# final_schematic_power_consumption_board.net
KiCad netlist of a schematic drawn in EAGLE
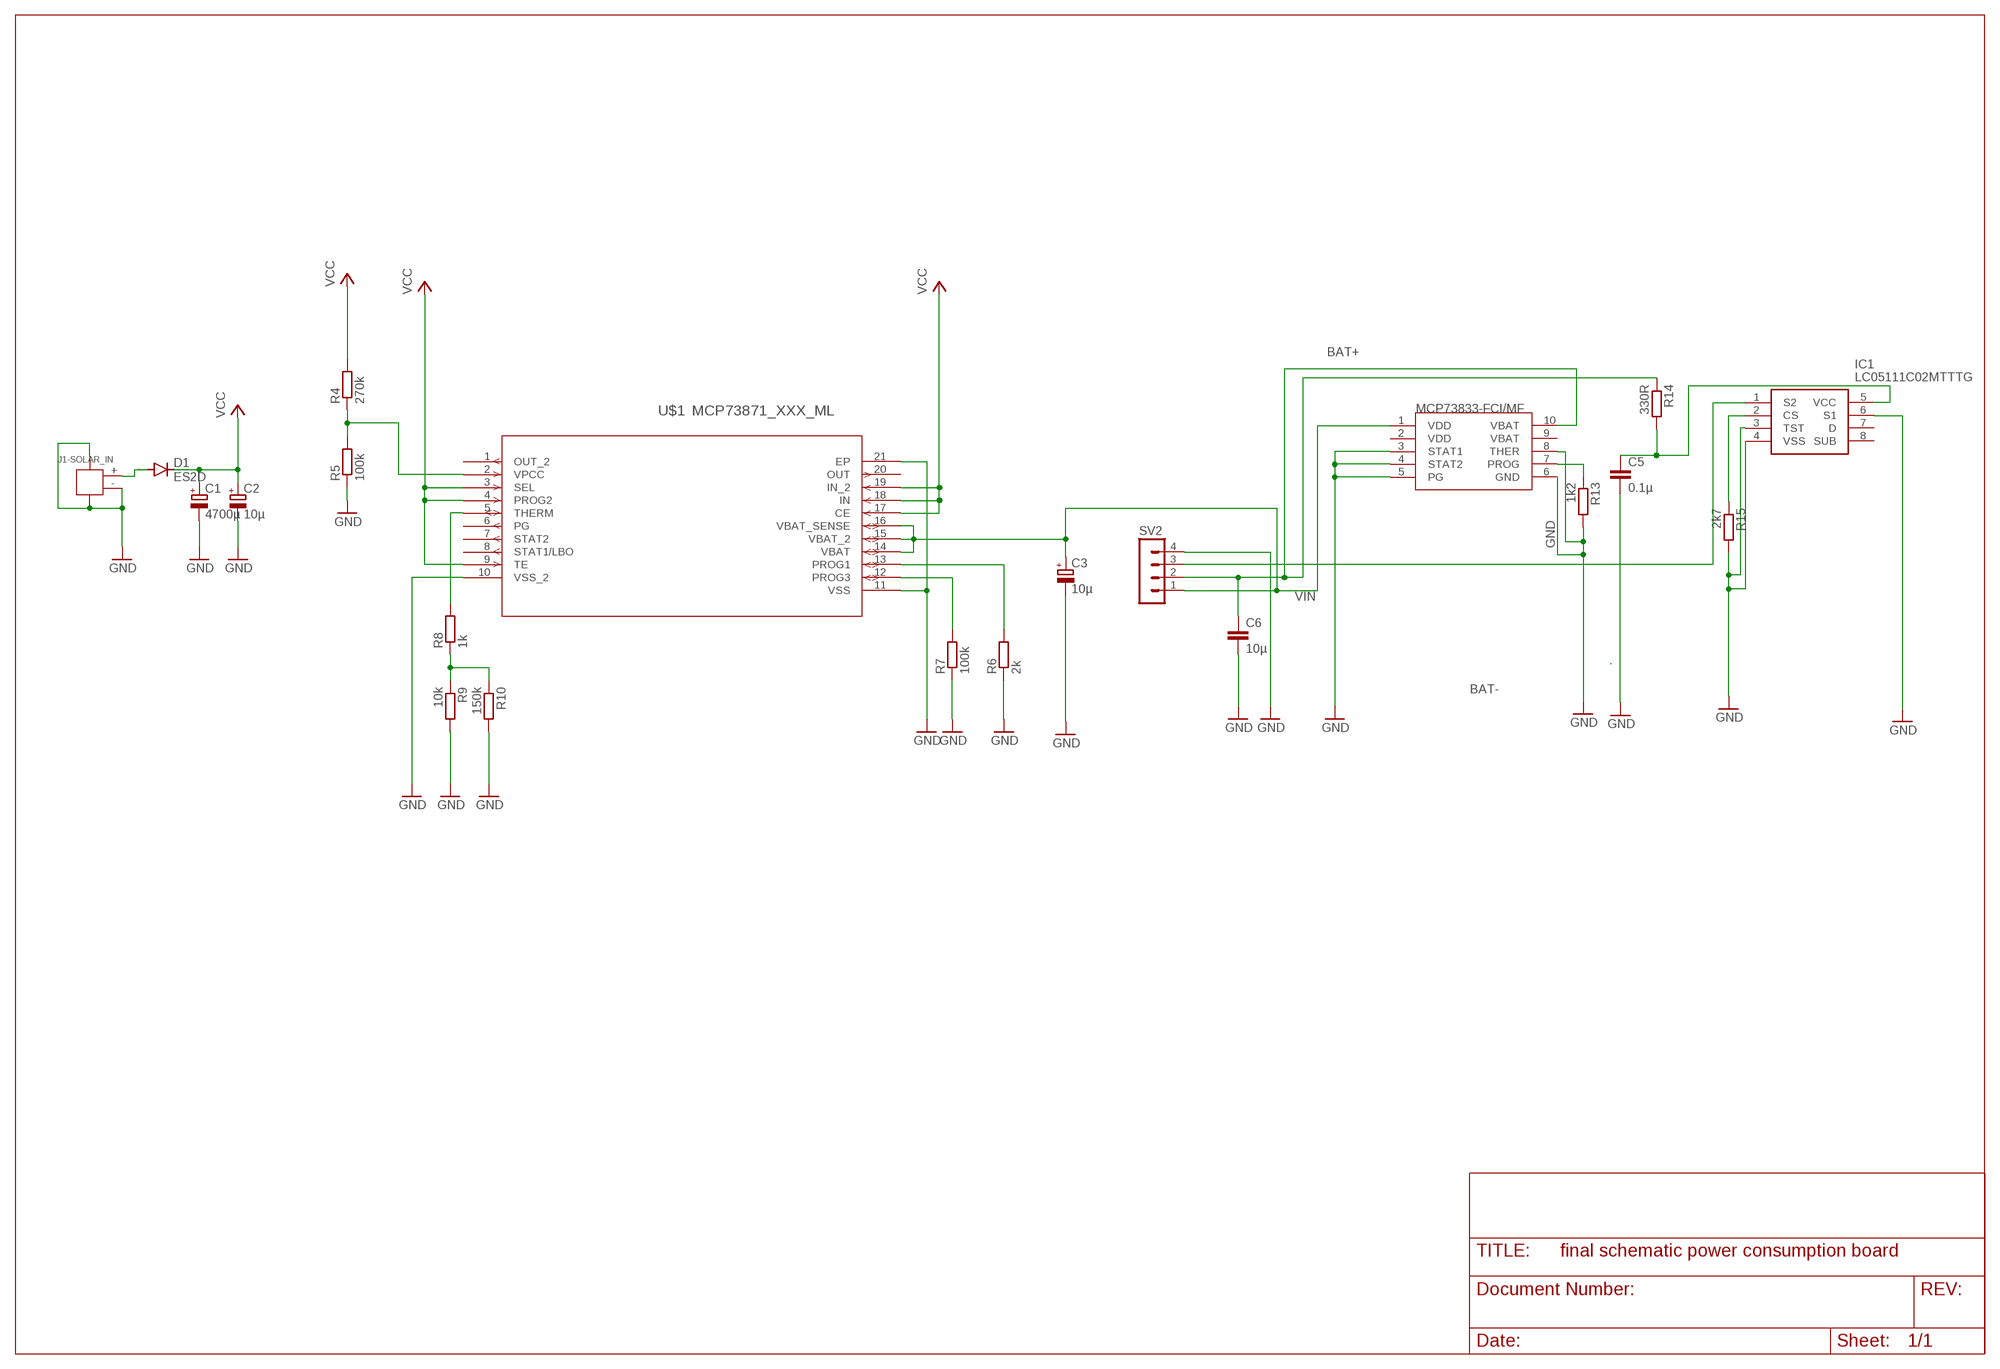
[diagram p0: schematic, sheet 1]

(export (version "E")
  (design (tool "Eeschema 10.0.6"))
  (components
    (comp (ref "C1")
      (value "4700µ")
      (footprint "eagle-import:153CLV-0505")
      (libsource (lib "eagle-import") (part "CPOL-EU153CLV-0505"))
    )
    (comp (ref "C2")
      (value "10µ")
      (footprint "eagle-import:153CLV-0505")
      (libsource (lib "eagle-import") (part "CPOL-EU153CLV-0505"))
    )
    (comp (ref "C3")
      (value "10µ")
      (footprint "eagle-import:153CLV-0505")
      (libsource (lib "eagle-import") (part "CPOL-EU153CLV-0505"))
    )
    (comp (ref "C5")
      (value "0.1µ")
      (footprint "eagle-import:C1206")
      (libsource (lib "eagle-import") (part "C-EUC1206"))
    )
    (comp (ref "C6")
      (value "10µ")
      (footprint "eagle-import:C1206")
      (libsource (lib "eagle-import") (part "C-EUC1206"))
    )
    (comp (ref "D1")
      (value "ES2D")
      (footprint "eagle-import:SMB")
      (libsource (lib "eagle-import") (part "ES2D"))
    )
    (comp (ref "IC1")
      (value "LC05111C02MTTTG")
      (footprint "eagle-import:LC05111C02MTTTG")
      (fields
        (field (name "MOUSER_PART_NUMBER") "863-LC05111C02MTTTG")
        (field (name "RS_PART_NUMBER") "8427787P")
      )
      (libsource (lib "eagle-import") (part "LC05111C02MTTTG"))
    )
    (comp (ref "J1-SOLAR_IN")
      (value "CONN-HEADER-SMD-PH-SIDE-(2P-2.0MM)")
      (footprint "eagle-import:HW2-SMD-2.0-90D")
      (libsource (lib "eagle-import") (part "CONN-HEADER-SMD-PH-SIDE-(2P-2.0MM)"))
    )
    (comp (ref "R4")
      (value "270k")
      (footprint "eagle-import:R0603")
      (libsource (lib "eagle-import") (part "R-EU_R0603"))
    )
    (comp (ref "R5")
      (value "100k")
      (footprint "eagle-import:R0603")
      (libsource (lib "eagle-import") (part "R-EU_R0603"))
    )
    (comp (ref "R6")
      (value "2k")
      (footprint "eagle-import:R0603")
      (libsource (lib "eagle-import") (part "R-EU_R0603"))
    )
    (comp (ref "R7")
      (value "100k")
      (footprint "eagle-import:R0603")
      (libsource (lib "eagle-import") (part "R-EU_R0603"))
    )
    (comp (ref "R8")
      (value "1k")
      (footprint "eagle-import:R0603")
      (libsource (lib "eagle-import") (part "R-EU_R0603"))
    )
    (comp (ref "R9")
      (value "10k")
      (footprint "eagle-import:R0603")
      (libsource (lib "eagle-import") (part "R-EU_R0603"))
    )
    (comp (ref "R10")
      (value "150k")
      (footprint "eagle-import:R0603")
      (libsource (lib "eagle-import") (part "R-EU_R0603"))
    )
    (comp (ref "R13")
      (value "1k2")
      (footprint "eagle-import:R1206W")
      (libsource (lib "eagle-import") (part "R-EU_R1206W"))
    )
    (comp (ref "R14")
      (value "330R")
      (footprint "eagle-import:R1206W")
      (libsource (lib "eagle-import") (part "R-EU_R1206W"))
    )
    (comp (ref "R15")
      (value "2k7")
      (footprint "eagle-import:R1206W")
      (libsource (lib "eagle-import") (part "R-EU_R1206W"))
    )
    (comp (ref "SV2")
      (value "MA04-1")
      (footprint "eagle-import:MA04-1")
      (libsource (lib "eagle-import") (part "MA04-1"))
    )
    (comp (ref "U$1")
      (value "MCP73871_XXX_ML")
      (footprint "eagle-import:QFN20_4X4MC")
      (libsource (lib "eagle-import") (part "MCP73871_XXX_ML"))
    )
    (comp (ref "U$3")
      (value "MCP73833-FCI/MF")
      (footprint "eagle-import:SOP50P490X110-10N")
      (libsource (lib "eagle-import") (part "MCP73833-FCI/MF"))
    )
  )
  (nets
    (net (code "1") (name "/BAT+") (class "Default")
      (node (ref "C6") (pin "1") (pinfunction "1_1") (pintype "passive"))
      (node (ref "R14") (pin "1") (pinfunction "1_1") (pintype "passive"))
      (node (ref "SV2") (pin "2") (pinfunction "2_2") (pintype "passive"))
      (node (ref "U$3") (pin "10") (pinfunction "VBAT_10") (pintype "bidirectional"))
    )
    (net (code "2") (name "/BAT-") (class "Default")
      (node (ref "IC1") (pin "1") (pinfunction "S2_1") (pintype "bidirectional"))
      (node (ref "SV2") (pin "3") (pinfunction "3_3") (pintype "passive"))
    )
    (net (code "3") (name "/VIN") (class "Default")
      (node (ref "C3") (pin "+") (pinfunction "+_+") (pintype "passive"))
      (node (ref "SV2") (pin "1") (pinfunction "1_1") (pintype "passive"))
      (node (ref "U$1") (pin "14") (pinfunction "VBAT_14") (pintype "bidirectional"))
      (node (ref "U$1") (pin "15") (pinfunction "VBAT_2_15") (pintype "bidirectional"))
      (node (ref "U$1") (pin "16") (pinfunction "VBAT_SENSE_16") (pintype "bidirectional"))
      (node (ref "U$3") (pin "1") (pinfunction "VDD_1") (pintype "bidirectional"))
    )
    (net (code "4") (name "GND") (class "Default")
      (node (ref "C1") (pin "-") (pinfunction "-_-") (pintype "passive"))
      (node (ref "C2") (pin "-") (pinfunction "-_-") (pintype "passive"))
      (node (ref "C3") (pin "-") (pinfunction "-_-") (pintype "passive"))
      (node (ref "C5") (pin "2") (pinfunction "2_2") (pintype "passive"))
      (node (ref "C6") (pin "2") (pinfunction "2_2") (pintype "passive"))
      (node (ref "IC1") (pin "3") (pinfunction "TST_3") (pintype "bidirectional"))
      (node (ref "IC1") (pin "4") (pinfunction "VSS_4") (pintype "bidirectional"))
      (node (ref "IC1") (pin "6") (pinfunction "S1_6") (pintype "bidirectional"))
      (node (ref "J1-SOLAR_IN") (pin "-") (pinfunction "2_-") (pintype "bidirectional"))
      (node (ref "J1-SOLAR_IN") (pin "3") (pinfunction "3_3") (pintype "bidirectional"))
      (node (ref "J1-SOLAR_IN") (pin "4") (pinfunction "4_4") (pintype "bidirectional"))
      (node (ref "R10") (pin "2") (pinfunction "2_2") (pintype "passive"))
      (node (ref "R13") (pin "2") (pinfunction "2_2") (pintype "passive"))
      (node (ref "R15") (pin "2") (pinfunction "2_2") (pintype "passive"))
      (node (ref "R5") (pin "1") (pinfunction "1_1") (pintype "passive"))
      (node (ref "R6") (pin "1") (pinfunction "1_1") (pintype "passive"))
      (node (ref "R7") (pin "1") (pinfunction "1_1") (pintype "passive"))
      (node (ref "R9") (pin "2") (pinfunction "2_2") (pintype "passive"))
      (node (ref "SV2") (pin "4") (pinfunction "4_4") (pintype "passive"))
      (node (ref "U$1") (pin "10") (pinfunction "VSS_2_10") (pintype "power_in"))
      (node (ref "U$1") (pin "11") (pinfunction "VSS_11") (pintype "power_in"))
      (node (ref "U$1") (pin "21") (pinfunction "EP_21") (pintype "passive"))
      (node (ref "U$3") (pin "3") (pinfunction "STAT1_3") (pintype "bidirectional"))
      (node (ref "U$3") (pin "4") (pinfunction "STAT2_4") (pintype "bidirectional"))
      (node (ref "U$3") (pin "5") (pinfunction "PG_5") (pintype "bidirectional"))
      (node (ref "U$3") (pin "6") (pinfunction "GND_6") (pintype "bidirectional"))
      (node (ref "U$3") (pin "8") (pinfunction "THER_8") (pintype "bidirectional"))
    )
    (net (code "5") (name "Net-(IC1-CS)") (class "Default")
      (node (ref "IC1") (pin "2") (pinfunction "CS_2") (pintype "bidirectional"))
      (node (ref "R15") (pin "1") (pinfunction "1_1") (pintype "passive"))
    )
    (net (code "6") (name "Net-(IC1-VCC)") (class "Default")
      (node (ref "C5") (pin "1") (pinfunction "1_1") (pintype "passive"))
      (node (ref "IC1") (pin "5") (pinfunction "VCC_5") (pintype "bidirectional"))
      (node (ref "R14") (pin "2") (pinfunction "2_2") (pintype "passive"))
    )
    (net (code "7") (name "Net-(J1-SOLAR_IN-1)") (class "Default")
      (node (ref "D1") (pin "A") (pinfunction "A_A") (pintype "passive"))
      (node (ref "J1-SOLAR_IN") (pin "+") (pinfunction "1_+") (pintype "bidirectional"))
    )
    (net (code "8") (name "Net-(R10-Pad1)") (class "Default")
      (node (ref "R10") (pin "1") (pinfunction "1_1") (pintype "passive"))
      (node (ref "R8") (pin "1") (pinfunction "1_1") (pintype "passive"))
      (node (ref "R9") (pin "1") (pinfunction "1_1") (pintype "passive"))
    )
    (net (code "9") (name "Net-(U$1-PROG1)") (class "Default")
      (node (ref "R6") (pin "2") (pinfunction "2_2") (pintype "passive"))
      (node (ref "U$1") (pin "13") (pinfunction "PROG1_13") (pintype "bidirectional"))
    )
    (net (code "10") (name "Net-(U$1-PROG3)") (class "Default")
      (node (ref "R7") (pin "2") (pinfunction "2_2") (pintype "passive"))
      (node (ref "U$1") (pin "12") (pinfunction "PROG3_12") (pintype "bidirectional"))
    )
    (net (code "11") (name "Net-(U$1-THERM)") (class "Default")
      (node (ref "R8") (pin "2") (pinfunction "2_2") (pintype "passive"))
      (node (ref "U$1") (pin "5") (pinfunction "THERM_5") (pintype "bidirectional"))
    )
    (net (code "12") (name "Net-(U$1-VPCC)") (class "Default")
      (node (ref "R4") (pin "1") (pinfunction "1_1") (pintype "passive"))
      (node (ref "R5") (pin "2") (pinfunction "2_2") (pintype "passive"))
      (node (ref "U$1") (pin "2") (pinfunction "VPCC_2") (pintype "input"))
    )
    (net (code "13") (name "Net-(U$3-PROG)") (class "Default")
      (node (ref "R13") (pin "1") (pinfunction "1_1") (pintype "passive"))
      (node (ref "U$3") (pin "7") (pinfunction "PROG_7") (pintype "bidirectional"))
    )
    (net (code "14") (name "VCC") (class "Default")
      (node (ref "C1") (pin "+") (pinfunction "+_+") (pintype "passive"))
      (node (ref "C2") (pin "+") (pinfunction "+_+") (pintype "passive"))
      (node (ref "D1") (pin "C") (pinfunction "C_C") (pintype "passive"))
      (node (ref "R4") (pin "2") (pinfunction "2_2") (pintype "passive"))
      (node (ref "U$1") (pin "17") (pinfunction "CE_17") (pintype "input"))
      (node (ref "U$1") (pin "18") (pinfunction "IN_18") (pintype "input"))
      (node (ref "U$1") (pin "19") (pinfunction "IN_2_19") (pintype "input"))
      (node (ref "U$1") (pin "3") (pinfunction "SEL_3") (pintype "input"))
      (node (ref "U$1") (pin "4") (pinfunction "PROG2_4") (pintype "input"))
      (node (ref "U$1") (pin "9") (pinfunction "TE_9") (pintype "input"))
    )
    (net (code "15") (name "unconnected-(IC1-D-Pad7)") (class "Default")
      (node (ref "IC1") (pin "7") (pinfunction "D_7") (pintype "bidirectional"))
    )
    (net (code "16") (name "unconnected-(IC1-SUB-Pad8)") (class "Default")
      (node (ref "IC1") (pin "8") (pinfunction "SUB_8") (pintype "bidirectional"))
    )
    (net (code "17") (name "unconnected-(U$1-OUT-Pad20)") (class "Default")
      (node (ref "U$1") (pin "20") (pinfunction "OUT_20") (pintype "output"))
    )
    (net (code "18") (name "unconnected-(U$1-OUT_2-Pad1)") (class "Default")
      (node (ref "U$1") (pin "1") (pinfunction "OUT_2_1") (pintype "output"))
    )
    (net (code "19") (name "unconnected-(U$1-PG-Pad6)") (class "Default")
      (node (ref "U$1") (pin "6") (pinfunction "PG_6") (pintype "output"))
    )
    (net (code "20") (name "unconnected-(U$1-STAT1{slash}LBO-Pad8)") (class "Default")
      (node (ref "U$1") (pin "8") (pinfunction "STAT1/LBO_8") (pintype "output"))
    )
    (net (code "21") (name "unconnected-(U$1-STAT2-Pad7)") (class "Default")
      (node (ref "U$1") (pin "7") (pinfunction "STAT2_7") (pintype "output"))
    )
    (net (code "22") (name "unconnected-(U$3-VBAT-Pad9)") (class "Default")
      (node (ref "U$3") (pin "9") (pinfunction "VBAT_9") (pintype "bidirectional"))
    )
    (net (code "23") (name "unconnected-(U$3-VDD-Pad2)") (class "Default")
      (node (ref "U$3") (pin "2") (pinfunction "VDD_2") (pintype "bidirectional"))
    )
  )
)
